# Doorbellv1_1.net
KiCad netlist of a schematic drawn in Altium Designer
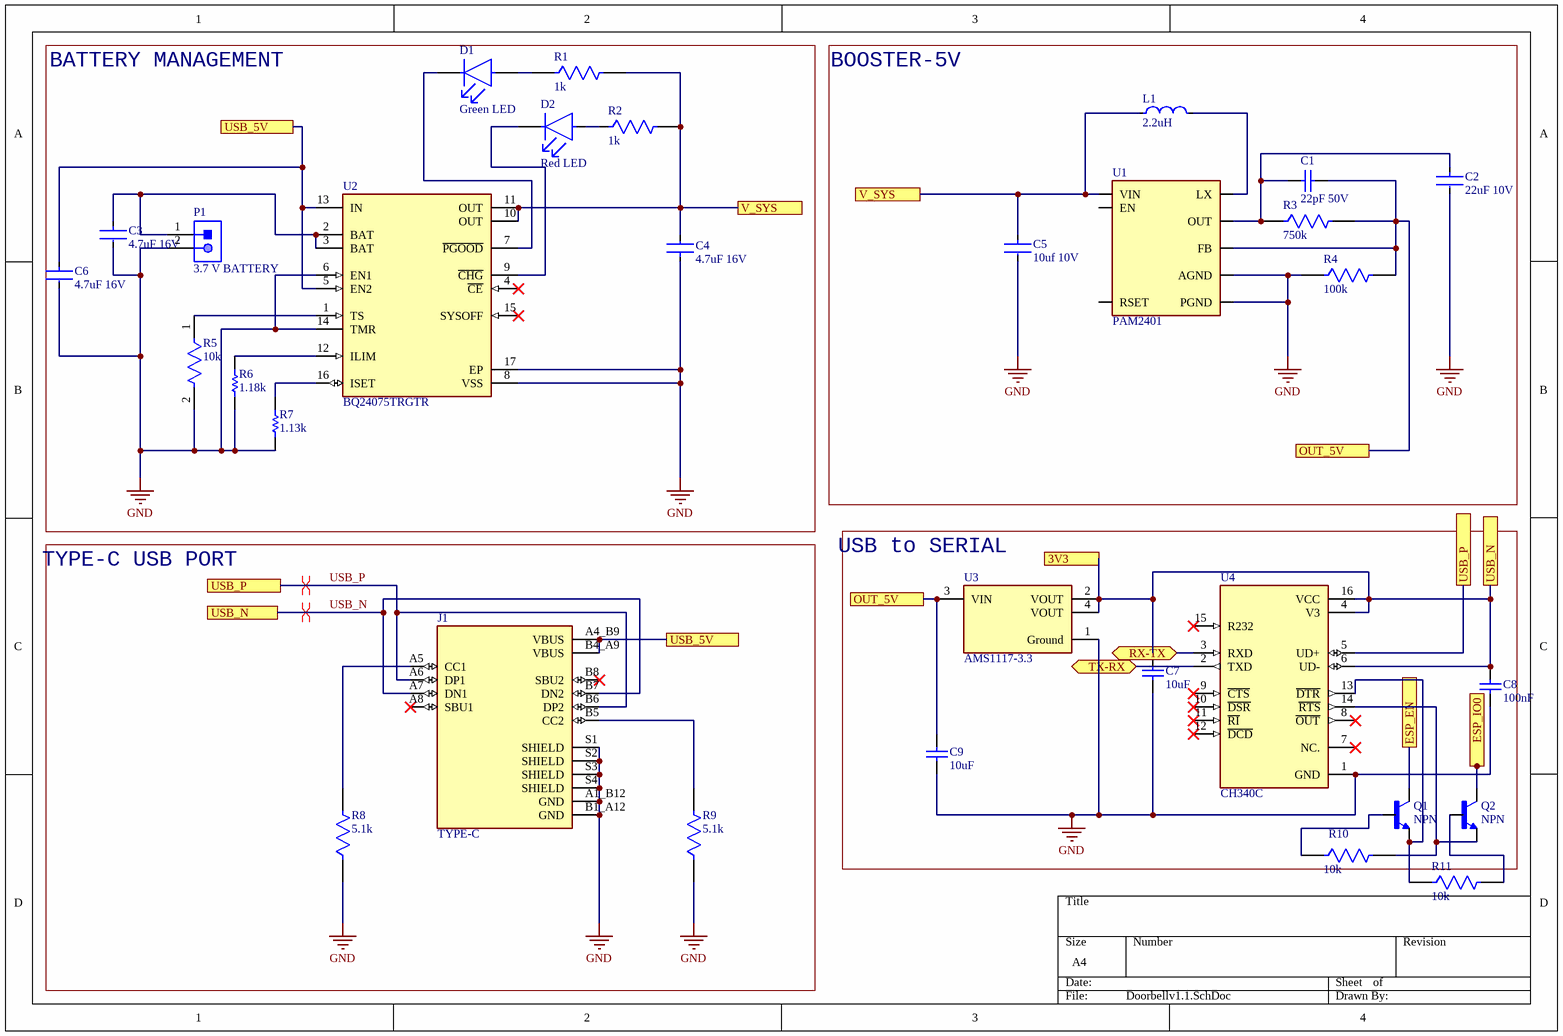
[diagram p0: Doorbellv1.1.SchDoc]

(export (version "E")
  (design (tool "Eeschema 10.0.6"))
  (components
    (comp (ref "C1")
      (value "22pF 50V")
      (footprint "CAPC0805(2012)145_N")
      (description "CAP 22pF 50V ±1% 0805 (2012 Metric) Thickness 1.45mm SMD")
      (fields (field (name "TOLERANCE") "Â±1%"))
      (libsource (lib "Altium Content Vault") (part "CAP"))
    )
    (comp (ref "C2")
      (value "22uF 10V")
      (footprint "FP-C0805C226M8PACTU-MFG")
      (description "CAP CER 22UF 10V X5R 0805")
      (fields (field (name "TOLERANCE") "20%") (field (name "VOLTAGE") "10V"))
      (libsource (lib "Altium Content Vault") (part "02cd4be3c70576c341d710602a673aa"))
    )
    (comp (ref "C3")
      (value "4.7uF 16V")
      (footprint "FP-GRM21B-0_15-MFG")
      (description "Chip Multilayer Ceramic Capacitors for General Purpose, 0805, 4.7uF, X7R, 15%, 20%, 16V")
      (fields (field (name "TOLERANCE") "20%"))
      (libsource (lib "Altium Content Vault") (part "b4654b650e69147ec39a6b967a45e02"))
    )
    (comp (ref "C4")
      (value "4.7uF 16V")
      (footprint "FP-GRM21B-0_15-MFG")
      (description "Chip Multilayer Ceramic Capacitors for General Purpose, 0805, 4.7uF, X7R, 15%, 20%, 16V")
      (fields (field (name "TOLERANCE") "20%"))
      (libsource (lib "Altium Content Vault") (part "b4654b650e69147ec39a6b967a45e02"))
    )
    (comp (ref "C5")
      (value "10uf 10V")
      (footprint "FP-C0805X106K8RACAUTO-MFG")
      (fields (field (name "TOLERANCE") "10%"))
      (libsource (lib "Altium Content Vault") (part "b4654b650e69147ec39a6b967a45e02"))
    )
    (comp (ref "C6")
      (value "4.7uF 16V")
      (footprint "FP-GRM21B-0_15-MFG")
      (description "Chip Multilayer Ceramic Capacitors for General Purpose, 0805, 4.7uF, X7R, 15%, 20%, 16V")
      (fields (field (name "TOLERANCE") "20%"))
      (libsource (lib "Altium Content Vault") (part "b4654b650e69147ec39a6b967a45e02"))
    )
    (comp (ref "C7")
      (value "10uF")
      (footprint "CAPC2013X140X50ML20T25")
      (fields
        (field (name "PART NUMBER") "08056D106KAT4A")
        (field (name "MANUFACTURER") "AVX Interconnect / Elco")
      )
      (libsource (lib "Altium Content Vault") (part "CAP"))
    )
    (comp (ref "C8")
      (value "100nF")
      (footprint "CAPC1608X90X35NL15T15")
      (fields
        (field (name "MANUFACTURER") "AVX Interconnect / Elco")
        (field (name "PART NUMBER") "06035C104MAT2A")
      )
      (libsource (lib "Altium Content Vault") (part "CAP"))
    )
    (comp (ref "C9")
      (value "10uF")
      (footprint "CAPC2013X140X50ML20T25")
      (fields
        (field (name "PART NUMBER") "08056D106KAT4A")
        (field (name "MANUFACTURER") "AVX Interconnect / Elco")
      )
      (libsource (lib "Altium Content Vault") (part "CAP"))
    )
    (comp (ref "D1")
      (value "Green LED")
      (footprint "FP-APHCM2012CGCK-F01-MFG")
      (description "LED GREEN CLEAR CHIP SMD")
      (libsource (lib "Altium Content Vault") (part "8706943c75ba83719d021d2fdc84c58"))
    )
    (comp (ref "D2")
      (value "Red LED")
      (footprint "FP-LS_R976-MFG")
      (description "LED RED DIFFUSED 0805 SMD")
      (libsource (lib "Altium Content Vault") (part "8706943c75ba83719d021d2fdc84c58"))
    )
    (comp (ref "J1")
      (value "TYPE-C")
      (footprint "HRO_TYPE-C-31-M-12")
      (description "USB Connectors 24 Receptacle 1 8.94*7.3mm RoHS")
      (fields (field (name "MF") "HRO Electronics Co., Ltd.") (field (name "MP") "TYPE-C-31-M-12"))
      (libsource (lib "TYPE-C-31-M-12") (part "TYPE-C-31-M-12"))
    )
    (comp (ref "L1")
      (value "2.2uH")
      (footprint "FP-NR4018-MFG")
      (description "SMD Power Inductors 2.2uH ±20% 2.2A 50.4mΩ")
      (fields (field (name "TOLERANCE") "20%"))
      (libsource (lib "Altium Content Vault") (part "725321dda6339637d4d059423bc1c3c"))
    )
    (comp (ref "P1")
      (value "3.7 V BATTERY")
      (footprint "JST-S2B-PH-K-S_V")
      (fields (field (name "TOLERANCE") "20%"))
      (libsource (lib "Altium Content Vault") (part "CN-1P-M-R2"))
    )
    (comp (ref "Q1")
      (value "NPN")
      (footprint "TRANS_SS8050-G")
      (description "Bipolar (BJT) Transistor NPN 25 V 1.5 A 100MHz 300 mW Surface Mount SOT-23-3")
      (fields (field (name "DIGI-KEY_PART_NUMBER") "641-1790-2-ND") (field (name "MP") "SS8050G"))
      (libsource (lib "SS8050-G (1)") (part "SS8050-G"))
    )
    (comp (ref "Q2")
      (value "NPN")
      (footprint "TRANS_SS8050-G")
      (description "Bipolar (BJT) Transistor NPN 25 V 1.5 A 100MHz 300 mW Surface Mount SOT-23-3")
      (fields (field (name "DIGI-KEY_PART_NUMBER") "641-1790-2-ND") (field (name "MP") "SS8050G"))
      (libsource (lib "SS8050-G (1)") (part "SS8050-G"))
    )
    (comp (ref "R1")
      (value "1k")
      (footprint "FP-TFCR0805-IPC_A")
      (description "RES Thin Film,  1kΩ, 0.1%, 0.1W, 25ppm/°C, 0805")
      (libsource (lib "Altium Content Vault") (part "1029c3af85768c4190bb7ad29bc67b5"))
    )
    (comp (ref "R2")
      (value "1k")
      (footprint "FP-TFCR0805-IPC_A")
      (description "RES Thin Film,  1kΩ, 0.1%, 0.1W, 25ppm/°C, 0805")
      (libsource (lib "Altium Content Vault") (part "1029c3af85768c4190bb7ad29bc67b5"))
    )
    (comp (ref "R3")
      (value "750k")
      (footprint "FP-AC0805-MFG")
      (description "AC Series 0805 750 kO ±1% 0.125 W ±100 ppm/°C SMT Thick Film Chip Resistor")
      (fields (field (name "TOLERANCE") "0.01") (field (name "MANUFACTURER") "Yageo"))
      (libsource (lib "Altium Content Vault") (part "1029c3af85768c4190bb7ad29bc67b5"))
    )
    (comp (ref "R4")
      (value "100k")
      (footprint "FP-CRCW0805-e3-IPC_A")
      (description "RES Thick Film, 100kΩ, 1%, 0.125W, 100ppm/°C, 0805")
      (fields (field (name "TOLERANCE") "1%"))
      (libsource (lib "Altium Content Vault") (part "1029c3af85768c4190bb7ad29bc67b5"))
    )
    (comp (ref "R5")
      (value "10k")
      (footprint "FP-RN732B-MFG")
      (description "10kΩ ±0.1% 0.125W, 1/8W Chip Resistor 1206 (3216 Metric) Moisture Resistant Thin Film")
      (fields (field (name "TOLERANCE") "0.1%"))
      (libsource (lib "") (part "1029c3af85768c4190bb7ad29bc67b5_1"))
    )
    (comp (ref "R6")
      (value "1.18k")
      (footprint "RESC2013X60X35LL10T20")
      (fields (field (name "MANUFACTURER") "Yageo") (field (name "PART NUMBER") "RC0805FR-07118KL"))
      (libsource (lib "Altium Content Vault") (part "RES"))
    )
    (comp (ref "R7")
      (value "1.13k")
      (footprint "RESC0805(2012)_L")
      (description "1K13 0.125W 1% 0805 (2012 Metric)  SMD")
      (fields (field (name "TOLERANCE") "1 %") (field (name "POWER") "0.125 W"))
      (libsource (lib "Altium Content Vault") (part "RES"))
    )
    (comp (ref "R8")
      (value "5.1k")
      (footprint "FP-CRCW0603-C-MFG")
      (description "RES 5.1K OHM 1% 1/10W 0603")
      (fields (field (name "TOLERANCE") "1%"))
      (libsource (lib "Altium Content Vault") (part "1029c3af85768c4190bb7ad29bc67b5"))
    )
    (comp (ref "R9")
      (value "5.1k")
      (footprint "FP-CRCW0603-C-MFG")
      (description "RES 5.1K OHM 1% 1/10W 0603")
      (fields (field (name "TOLERANCE") "1%"))
      (libsource (lib "Altium Content Vault") (part "1029c3af85768c4190bb7ad29bc67b5"))
    )
    (comp (ref "R10")
      (value "10k")
      (footprint "FP-CPF0603-MFG")
      (description "RES SMD 10KΩ 0.5% 1/16W 0603")
      (fields
        (field (name "OCTOPART") "https://octopart.com/cpf0603d10ke-te+connectivity-22737789")
        (field (name "MANUFACTURER") "TE Connectivity")
      )
      (libsource (lib "Altium Content Vault") (part "1029c3af85768c4190bb7ad29bc67b5"))
    )
    (comp (ref "R11")
      (value "10k")
      (footprint "FP-CPF0603-MFG")
      (description "RES SMD 10KΩ 0.5% 1/16W 0603")
      (fields
        (field (name "OCTOPART") "https://octopart.com/cpf0603d10ke-te+connectivity-22737789")
        (field (name "MANUFACTURER") "TE Connectivity")
      )
      (libsource (lib "Altium Content Vault") (part "1029c3af85768c4190bb7ad29bc67b5"))
    )
    (comp (ref "U1")
      (value "PAM2401")
      (footprint "MSOP8")
      (description "Conv DC-DC 0.9V to 4.75V Synchronous Step Up Single-Out 2.5V to 5V 12-Pin UDFN EP T/R")
      (fields (field (name "MF") "Diodes Zetex"))
      (libsource (lib "PAM2401 (1)") (part "PAM2401"))
    )
    (comp (ref "U2")
      (value "BQ24075TRGTR")
      (footprint "FP-RGT0016C-IPC_C")
      (description "IC LI-ION CHARGE/PWR MGMT 16QFN")
      (libsource (lib "Altium Content Vault") (part "3f433feb0ee0ec5b012f5b84e4d4986"))
    )
    (comp (ref "U3")
      (value "AMS1117-3.3")
      (footprint "FP-AMS1117-IPC_C")
      (description "LDO Voltage Regulators 1A, 3.3V")
      (fields
        (field (name "OCTOPART") "https://octopart.com/ams1117-3.3-advanced+monolithic+systems-25899300")
        (field (name "MANUFACTURER") "Advanced Monolithic Systems")
      )
      (libsource (lib "Altium Content Vault") (part "8bdbb5f8e77002000e30dd2845d0354"))
    )
    (comp (ref "U4")
      (value "CH340C")
      (footprint "SOIC127P600X180-16N")
      (description "USB to serial chip CH340")
      (fields (field (name "MF") "WCH"))
      (libsource (lib "CH340C (1)") (part "CH340C"))
    )
  )
  (nets
    (net (code "1") (name "/ESP_EN") (class "Default")
      (node (ref "Q1") (pin "3") (pinfunction "C_3") (pintype "passive"))
    )
    (net (code "2") (name "/ESP_IO0") (class "Default")
      (node (ref "Q2") (pin "3") (pinfunction "C_3") (pintype "passive"))
    )
    (net (code "3") (name "/OUT_5V") (class "Default")
      (node (ref "C1") (pin "2") (pinfunction "2_2") (pintype "passive"))
      (node (ref "C9") (pin "2") (pinfunction "2_2") (pintype "passive"))
      (node (ref "R3") (pin "2") (pinfunction "2_2") (pintype "passive"))
      (node (ref "R4") (pin "2") (pinfunction "2_2") (pintype "passive"))
      (node (ref "U1") (pin "5") (pinfunction "FB_5") (pintype "bidirectional"))
      (node (ref "U3") (pin "3") (pinfunction "VIN_3") (pintype "power_in"))
    )
    (net (code "4") (name "/RX-TX") (class "Default")
      (node (ref "U4") (pin "3") (pinfunction "RXD_3") (pintype "input"))
    )
    (net (code "5") (name "/TX-RX") (class "Default")
      (node (ref "U4") (pin "2") (pinfunction "TXD_2") (pintype "output"))
    )
    (net (code "6") (name "/USB_5V") (class "Default")
      (node (ref "C6") (pin "1") (pinfunction "1_1") (pintype "passive"))
      (node (ref "J1") (pin "A4_B9") (pinfunction "VBUS_A4_B9") (pintype "power_in"))
      (node (ref "J1") (pin "B4_A9") (pinfunction "VBUS_B4_A9") (pintype "power_in"))
      (node (ref "U2") (pin "13") (pinfunction "IN_13") (pintype "power_in"))
      (node (ref "U2") (pin "5") (pinfunction "EN2_5") (pintype "input"))
    )
    (net (code "7") (name "/USB_N") (class "Default")
      (node (ref "C7") (pin "2") (pinfunction "2_2") (pintype "passive"))
      (node (ref "C8") (pin "2") (pinfunction "2_2") (pintype "passive"))
      (node (ref "J1") (pin "A7") (pinfunction "DN1_A7") (pintype "bidirectional"))
      (node (ref "J1") (pin "B7") (pinfunction "DN2_B7") (pintype "bidirectional"))
      (node (ref "U3") (pin "2") (pinfunction "VOUT_2") (pintype "passive"))
      (node (ref "U3") (pin "4") (pinfunction "VOUT_4") (pintype "passive"))
      (node (ref "U4") (pin "16") (pinfunction "VCC_16") (pintype "power_in"))
      (node (ref "U4") (pin "4") (pinfunction "V3_4") (pintype "power_in"))
      (node (ref "U4") (pin "6") (pinfunction "UD-_6") (pintype "bidirectional"))
    )
    (net (code "8") (name "/USB_P") (class "Default")
      (node (ref "J1") (pin "A6") (pinfunction "DP1_A6") (pintype "bidirectional"))
      (node (ref "J1") (pin "B6") (pinfunction "DP2_B6") (pintype "bidirectional"))
      (node (ref "U4") (pin "5") (pinfunction "UD+_5") (pintype "bidirectional"))
    )
    (net (code "9") (name "/V_SYS") (class "Default")
      (node (ref "C4") (pin "2") (pinfunction "2_2") (pintype "passive"))
      (node (ref "C5") (pin "1") (pinfunction "1_1") (pintype "passive"))
      (node (ref "L1") (pin "1") (pinfunction "1_1") (pintype "passive"))
      (node (ref "R1") (pin "2") (pinfunction "2_2") (pintype "passive"))
      (node (ref "R2") (pin "2") (pinfunction "2_2") (pintype "passive"))
      (node (ref "U1") (pin "3") (pinfunction "VIN_3") (pintype "bidirectional"))
      (node (ref "U2") (pin "10") (pinfunction "OUT_10") (pintype "power_in"))
      (node (ref "U2") (pin "11") (pinfunction "OUT_11") (pintype "power_in"))
    )
    (net (code "10") (name "GND") (class "Default")
      (node (ref "C2") (pin "2") (pinfunction "2_2") (pintype "passive"))
      (node (ref "C3") (pin "2") (pinfunction "2_2") (pintype "passive"))
      (node (ref "C4") (pin "1") (pinfunction "1_1") (pintype "passive"))
      (node (ref "C5") (pin "2") (pinfunction "2_2") (pintype "passive"))
      (node (ref "C6") (pin "2") (pinfunction "2_2") (pintype "passive"))
      (node (ref "C7") (pin "1") (pinfunction "1_1") (pintype "passive"))
      (node (ref "C8") (pin "1") (pinfunction "1_1") (pintype "passive"))
      (node (ref "C9") (pin "1") (pinfunction "1_1") (pintype "passive"))
      (node (ref "J1") (pin "A1_B12") (pinfunction "GND_A1_B12") (pintype "power_in"))
      (node (ref "J1") (pin "B1_A12") (pinfunction "GND_B1_A12") (pintype "power_in"))
      (node (ref "J1") (pin "S1") (pinfunction "SHIELD_S1") (pintype "passive"))
      (node (ref "J1") (pin "S2") (pinfunction "SHIELD_S2") (pintype "passive"))
      (node (ref "J1") (pin "S3") (pinfunction "SHIELD_S3") (pintype "passive"))
      (node (ref "J1") (pin "S4") (pinfunction "SHIELD_S4") (pintype "passive"))
      (node (ref "P1") (pin "2") (pinfunction "2_2") (pintype "passive"))
      (node (ref "R4") (pin "1") (pinfunction "1_1") (pintype "passive"))
      (node (ref "R5") (pin "2") (pinfunction "2_2") (pintype "passive"))
      (node (ref "R6") (pin "1") (pinfunction "1_1") (pintype "passive"))
      (node (ref "R7") (pin "1") (pinfunction "1_1") (pintype "passive"))
      (node (ref "R8") (pin "1") (pinfunction "1_1") (pintype "passive"))
      (node (ref "R9") (pin "1") (pinfunction "1_1") (pintype "passive"))
      (node (ref "U1") (pin "4") (pinfunction "AGND_4") (pintype "bidirectional"))
      (node (ref "U1") (pin "8") (pinfunction "PGND_8") (pintype "bidirectional"))
      (node (ref "U2") (pin "14") (pinfunction "TMR_14") (pintype "passive"))
      (node (ref "U2") (pin "17") (pinfunction "EP_17") (pintype "power_in"))
      (node (ref "U2") (pin "6") (pinfunction "EN1_6") (pintype "input"))
      (node (ref "U2") (pin "8") (pinfunction "VSS_8") (pintype "power_in"))
      (node (ref "U3") (pin "1") (pinfunction "Ground_1") (pintype "power_in"))
      (node (ref "U4") (pin "1") (pinfunction "GND_1") (pintype "power_in"))
    )
    (net (code "11") (name "Net-(C3-Pad1)") (class "Default")
      (node (ref "C3") (pin "1") (pinfunction "1_1") (pintype "passive"))
      (node (ref "P1") (pin "1") (pinfunction "1_1") (pintype "passive"))
      (node (ref "U2") (pin "2") (pinfunction "BAT_2") (pintype "power_in"))
      (node (ref "U2") (pin "3") (pinfunction "BAT_3") (pintype "power_in"))
    )
    (net (code "12") (name "Net-(D1-A)") (class "Default")
      (node (ref "D1") (pin "2") (pinfunction "A_2") (pintype "passive"))
      (node (ref "R1") (pin "1") (pinfunction "1_1") (pintype "passive"))
    )
    (net (code "13") (name "Net-(D1-C)") (class "Default")
      (node (ref "D1") (pin "1") (pinfunction "C_1") (pintype "passive"))
      (node (ref "U2") (pin "7") (pinfunction "~{PGOOD}_7") (pintype "open_collector"))
    )
    (net (code "14") (name "Net-(D2-A)") (class "Default")
      (node (ref "D2") (pin "2") (pinfunction "A_2") (pintype "passive"))
      (node (ref "R2") (pin "1") (pinfunction "1_1") (pintype "passive"))
    )
    (net (code "15") (name "Net-(D2-C)") (class "Default")
      (node (ref "D2") (pin "1") (pinfunction "C_1") (pintype "passive"))
      (node (ref "U2") (pin "9") (pinfunction "~{CHG}_9") (pintype "open_collector"))
    )
    (net (code "16") (name "Net-(J1-CC1)") (class "Default")
      (node (ref "J1") (pin "A5") (pinfunction "CC1_A5") (pintype "bidirectional"))
      (node (ref "R8") (pin "2") (pinfunction "2_2") (pintype "passive"))
    )
    (net (code "17") (name "Net-(J1-CC2)") (class "Default")
      (node (ref "J1") (pin "B5") (pinfunction "CC2_B5") (pintype "bidirectional"))
      (node (ref "R9") (pin "2") (pinfunction "2_2") (pintype "passive"))
    )
    (net (code "18") (name "Net-(Q1-B)") (class "Default")
      (node (ref "Q1") (pin "1") (pinfunction "B_1") (pintype "passive"))
      (node (ref "R10") (pin "1") (pinfunction "1_1") (pintype "passive"))
    )
    (net (code "19") (name "Net-(Q1-E)") (class "Default")
      (node (ref "Q1") (pin "2") (pinfunction "E_2") (pintype "passive"))
      (node (ref "R11") (pin "1") (pinfunction "1_1") (pintype "passive"))
      (node (ref "U4") (pin "13") (pinfunction "~{DTR}_13") (pintype "output"))
    )
    (net (code "20") (name "Net-(Q2-B)") (class "Default")
      (node (ref "Q2") (pin "1") (pinfunction "B_1") (pintype "passive"))
      (node (ref "R11") (pin "2") (pinfunction "2_2") (pintype "passive"))
    )
    (net (code "21") (name "Net-(Q2-E)") (class "Default")
      (node (ref "Q2") (pin "2") (pinfunction "E_2") (pintype "passive"))
      (node (ref "R10") (pin "2") (pinfunction "2_2") (pintype "passive"))
      (node (ref "U4") (pin "14") (pinfunction "~{RTS}_14") (pintype "output"))
    )
    (net (code "22") (name "Net-(U1-LX)") (class "Default")
      (node (ref "L1") (pin "2") (pinfunction "2_2") (pintype "passive"))
      (node (ref "U1") (pin "1") (pinfunction "LX_1") (pintype "bidirectional"))
    )
    (net (code "23") (name "Net-(U1-OUT)") (class "Default")
      (node (ref "C1") (pin "1") (pinfunction "1_1") (pintype "passive"))
      (node (ref "C2") (pin "1") (pinfunction "1_1") (pintype "passive"))
      (node (ref "R3") (pin "1") (pinfunction "1_1") (pintype "passive"))
      (node (ref "U1") (pin "7") (pinfunction "OUT_7") (pintype "bidirectional"))
    )
    (net (code "24") (name "Net-(U2-ILIM)") (class "Default")
      (node (ref "R6") (pin "2") (pinfunction "2_2") (pintype "passive"))
      (node (ref "U2") (pin "12") (pinfunction "ILIM_12") (pintype "input"))
    )
    (net (code "25") (name "Net-(U2-ISET)") (class "Default")
      (node (ref "R7") (pin "2") (pinfunction "2_2") (pintype "passive"))
      (node (ref "U2") (pin "16") (pinfunction "ISET_16") (pintype "bidirectional"))
    )
    (net (code "26") (name "Net-(U2-TS)") (class "Default")
      (node (ref "R5") (pin "1") (pinfunction "1_1") (pintype "passive"))
      (node (ref "U2") (pin "1") (pinfunction "TS_1") (pintype "input"))
    )
    (net (code "27") (name "unconnected-(J1-SBU1-PadA8)") (class "Default")
      (node (ref "J1") (pin "A8") (pinfunction "SBU1_A8") (pintype "bidirectional+no_connect"))
    )
    (net (code "28") (name "unconnected-(J1-SBU2-PadB8)") (class "Default")
      (node (ref "J1") (pin "B8") (pinfunction "SBU2_B8") (pintype "bidirectional+no_connect"))
    )
    (net (code "29") (name "unconnected-(U1-EN-Pad2)") (class "Default")
      (node (ref "U1") (pin "2") (pinfunction "EN_2") (pintype "bidirectional"))
    )
    (net (code "30") (name "unconnected-(U1-RSET-Pad6)") (class "Default")
      (node (ref "U1") (pin "6") (pinfunction "RSET_6") (pintype "bidirectional"))
    )
    (net (code "31") (name "unconnected-(U2-SYSOFF-Pad15)") (class "Default")
      (node (ref "U2") (pin "15") (pinfunction "SYSOFF_15") (pintype "input+no_connect"))
    )
    (net (code "32") (name "unconnected-(U2-~{CE}-Pad4)") (class "Default")
      (node (ref "U2") (pin "4") (pinfunction "~{CE}_4") (pintype "input+no_connect"))
    )
    (net (code "33") (name "unconnected-(U4-NC.-Pad7)") (class "Default")
      (node (ref "U4") (pin "7") (pinfunction "NC._7") (pintype "passive+no_connect"))
    )
    (net (code "34") (name "unconnected-(U4-R232-Pad15)") (class "Default")
      (node (ref "U4") (pin "15") (pinfunction "R232_15") (pintype "input+no_connect"))
    )
    (net (code "35") (name "unconnected-(U4-~{CTS}-Pad9)") (class "Default")
      (node (ref "U4") (pin "9") (pinfunction "~{CTS}_9") (pintype "input+no_connect"))
    )
    (net (code "36") (name "unconnected-(U4-~{DCD}-Pad12)") (class "Default")
      (node (ref "U4") (pin "12") (pinfunction "~{DCD}_12") (pintype "input+no_connect"))
    )
    (net (code "37") (name "unconnected-(U4-~{DSR}-Pad10)") (class "Default")
      (node (ref "U4") (pin "10") (pinfunction "~{DSR}_10") (pintype "input+no_connect"))
    )
    (net (code "38") (name "unconnected-(U4-~{OUT}-Pad8)") (class "Default")
      (node (ref "U4") (pin "8") (pinfunction "~{OUT}_8") (pintype "output+no_connect"))
    )
    (net (code "39") (name "unconnected-(U4-~{RI}-Pad11)") (class "Default")
      (node (ref "U4") (pin "11") (pinfunction "~{RI}_11") (pintype "input+no_connect"))
    )
  )
)
